# ACC_GYRO_SENSOR.net
KiCad netlist of a schematic drawn in EAGLE
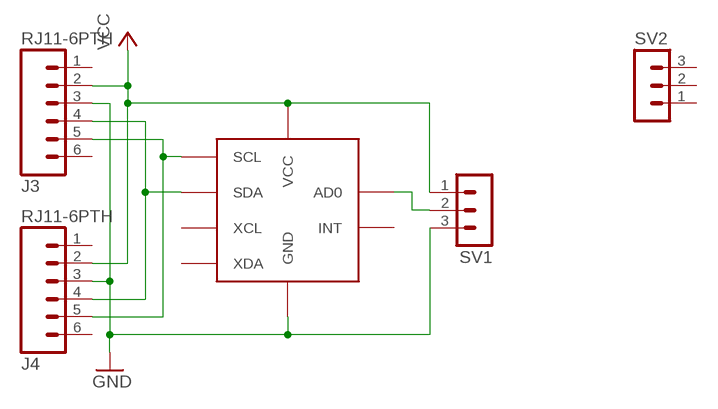
[diagram p0: schematic, sheet 1]

(export (version "E")
  (design (tool "Eeschema 10.0.6"))
  (components
    (comp (ref "J3")
      (value "RJ11-6PTH")
      (footprint "eagle-import:RJ11-6")
      (libsource (lib "eagle-import") (part "RJ11-6PTH"))
    )
    (comp (ref "J4")
      (value "RJ11-6PTH")
      (footprint "eagle-import:RJ11-6")
      (libsource (lib "eagle-import") (part "RJ11-6PTH"))
    )
    (comp (ref "SV1")
      (value "MA03-1")
      (footprint "eagle-import:MA03-1")
      (libsource (lib "eagle-import") (part "MA03-1"))
    )
    (comp (ref "SV2")
      (value "MA03-1")
      (footprint "eagle-import:MA03-1")
      (libsource (lib "eagle-import") (part "MA03-1"))
    )
    (comp (ref "U$1")
      (value "GY-521")
      (footprint "eagle-import:GY-521")
      (libsource (lib "eagle-import") (part "GY-521"))
    )
  )
  (nets
    (net (code "1") (name "GND") (class "Default")
      (node (ref "J3") (pin "3") (pinfunction "3_3") (pintype "passive"))
      (node (ref "J4") (pin "3") (pinfunction "3_3") (pintype "passive"))
      (node (ref "SV1") (pin "3") (pinfunction "3_3") (pintype "passive"))
      (node (ref "U$1") (pin "GND") (pinfunction "GND_GND") (pintype "bidirectional"))
    )
    (net (code "2") (name "Net-(J3-Pad4)") (class "Default")
      (node (ref "J3") (pin "4") (pinfunction "4_4") (pintype "passive"))
      (node (ref "J4") (pin "4") (pinfunction "4_4") (pintype "passive"))
      (node (ref "U$1") (pin "SDA") (pinfunction "SDA_SDA") (pintype "bidirectional"))
    )
    (net (code "3") (name "Net-(J3-Pad5)") (class "Default")
      (node (ref "J3") (pin "5") (pinfunction "5_5") (pintype "passive"))
      (node (ref "J4") (pin "5") (pinfunction "5_5") (pintype "passive"))
      (node (ref "U$1") (pin "SCL") (pinfunction "SCL_SCL") (pintype "bidirectional"))
    )
    (net (code "4") (name "Net-(SV1-Pad2)") (class "Default")
      (node (ref "SV1") (pin "2") (pinfunction "2_2") (pintype "passive"))
      (node (ref "U$1") (pin "AD0") (pinfunction "AD0_AD0") (pintype "bidirectional"))
    )
    (net (code "5") (name "VCC") (class "Default")
      (node (ref "J3") (pin "2") (pinfunction "2_2") (pintype "passive"))
      (node (ref "J4") (pin "2") (pinfunction "2_2") (pintype "passive"))
      (node (ref "SV1") (pin "1") (pinfunction "1_1") (pintype "passive"))
      (node (ref "U$1") (pin "VCC") (pinfunction "VCC_VCC") (pintype "bidirectional"))
    )
    (net (code "6") (name "unconnected-(J3-Pad1)") (class "Default")
      (node (ref "J3") (pin "1") (pinfunction "1_1") (pintype "passive"))
    )
    (net (code "7") (name "unconnected-(J3-Pad6)") (class "Default")
      (node (ref "J3") (pin "6") (pinfunction "6_6") (pintype "passive"))
    )
    (net (code "8") (name "unconnected-(J4-Pad1)") (class "Default")
      (node (ref "J4") (pin "1") (pinfunction "1_1") (pintype "passive"))
    )
    (net (code "9") (name "unconnected-(J4-Pad6)") (class "Default")
      (node (ref "J4") (pin "6") (pinfunction "6_6") (pintype "passive"))
    )
    (net (code "10") (name "unconnected-(SV2-Pad1)") (class "Default")
      (node (ref "SV2") (pin "1") (pinfunction "1_1") (pintype "passive"))
    )
    (net (code "11") (name "unconnected-(SV2-Pad2)") (class "Default")
      (node (ref "SV2") (pin "2") (pinfunction "2_2") (pintype "passive"))
    )
    (net (code "12") (name "unconnected-(SV2-Pad3)") (class "Default")
      (node (ref "SV2") (pin "3") (pinfunction "3_3") (pintype "passive"))
    )
    (net (code "13") (name "unconnected-(U$1-PadINT)") (class "Default")
      (node (ref "U$1") (pin "INT") (pinfunction "INT_INT") (pintype "bidirectional"))
    )
    (net (code "14") (name "unconnected-(U$1-PadXCL)") (class "Default")
      (node (ref "U$1") (pin "XCL") (pinfunction "XCL_XCL") (pintype "bidirectional"))
    )
    (net (code "15") (name "unconnected-(U$1-PadXDA)") (class "Default")
      (node (ref "U$1") (pin "XDA") (pinfunction "XDA_XDA") (pintype "bidirectional"))
    )
  )
)
